# Power_Distro_Board.net
KiCad netlist of a schematic drawn in EAGLE
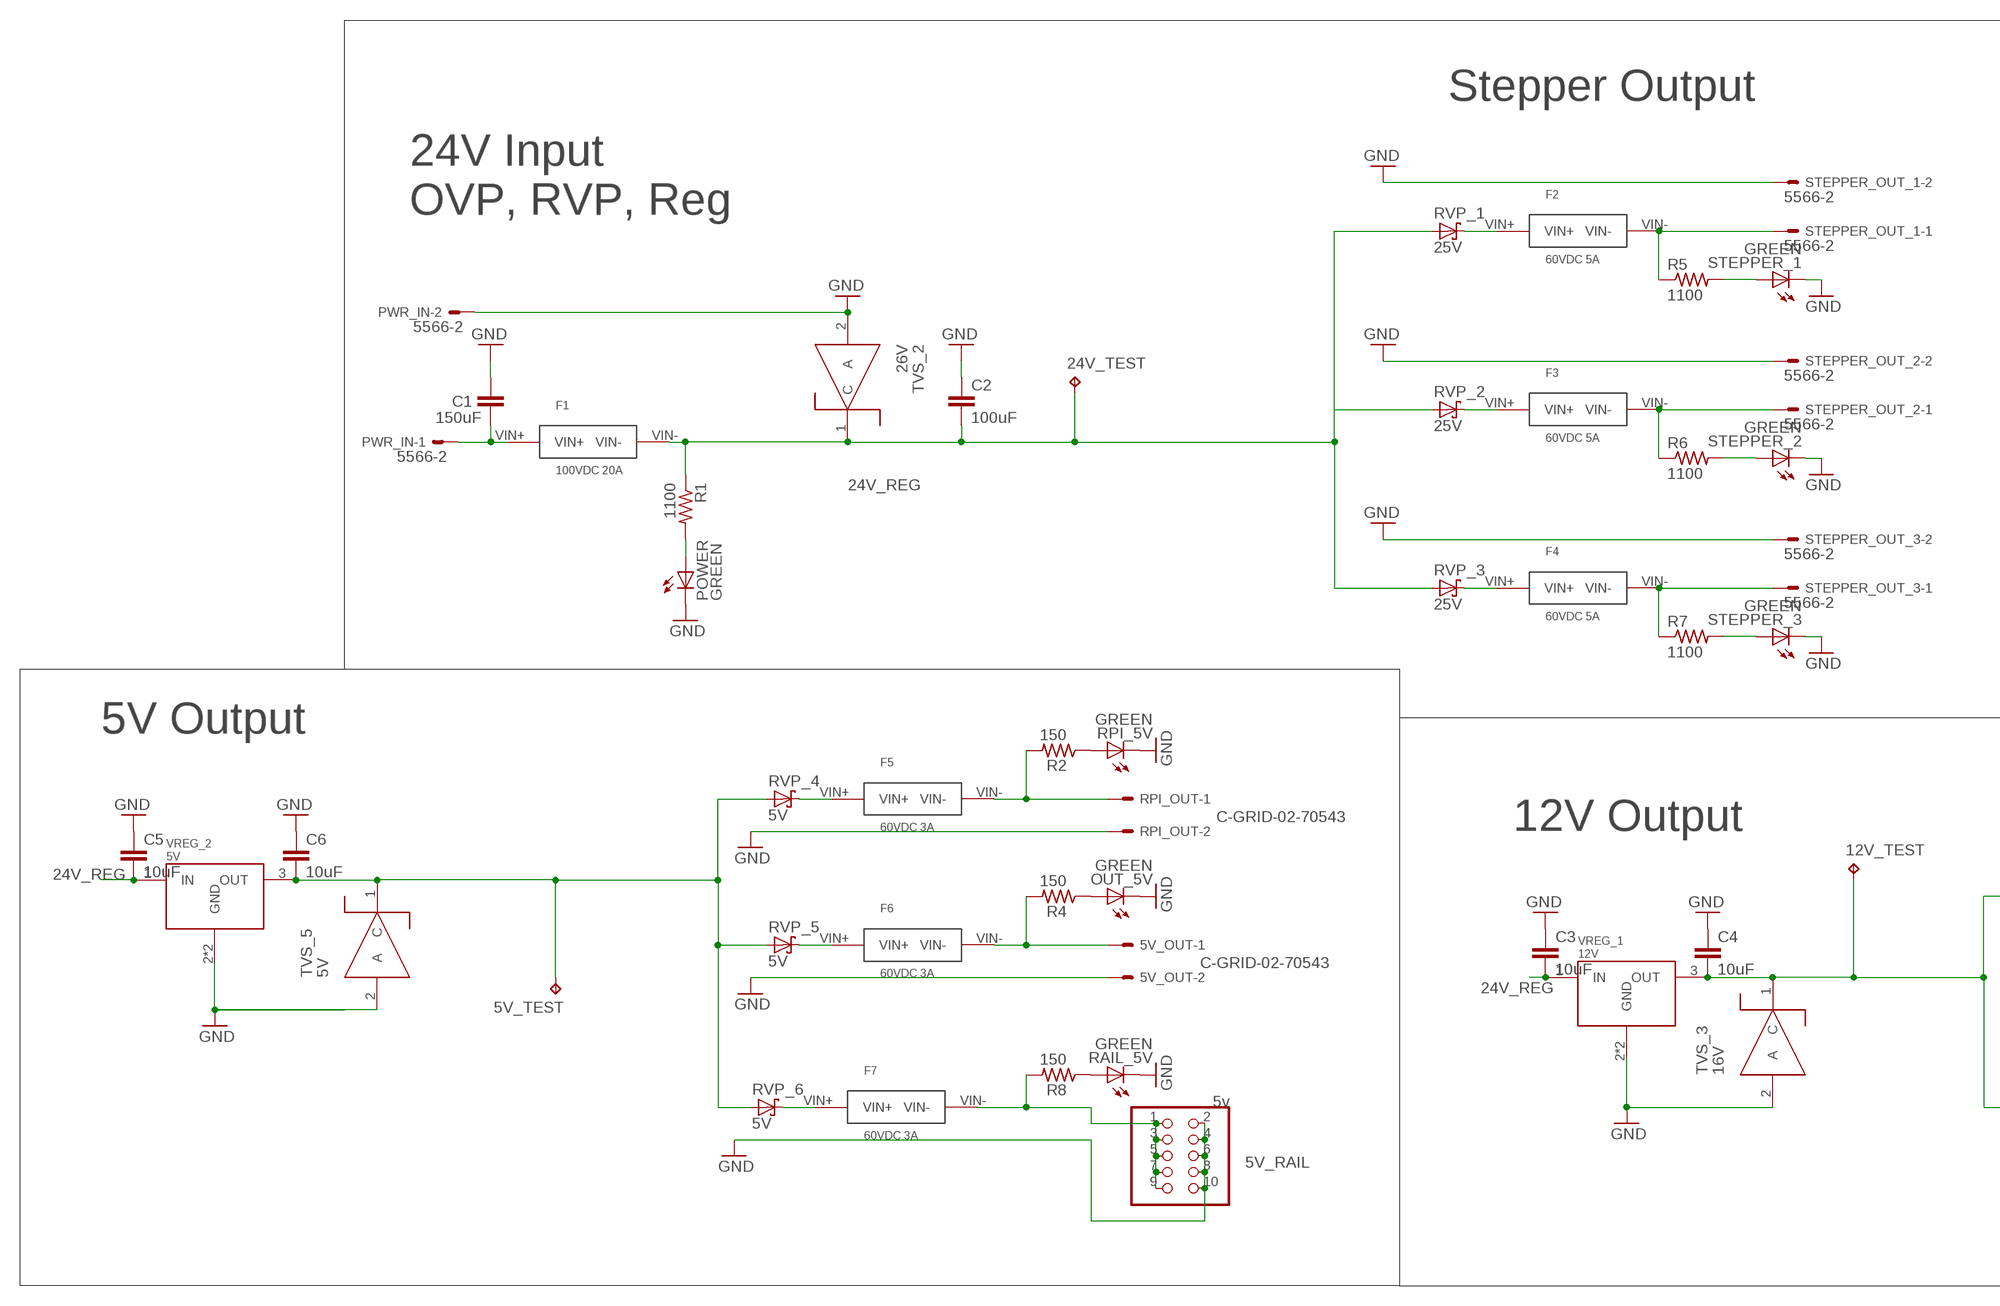
[diagram p0: schematic, sheet 1, part 1 of 2]
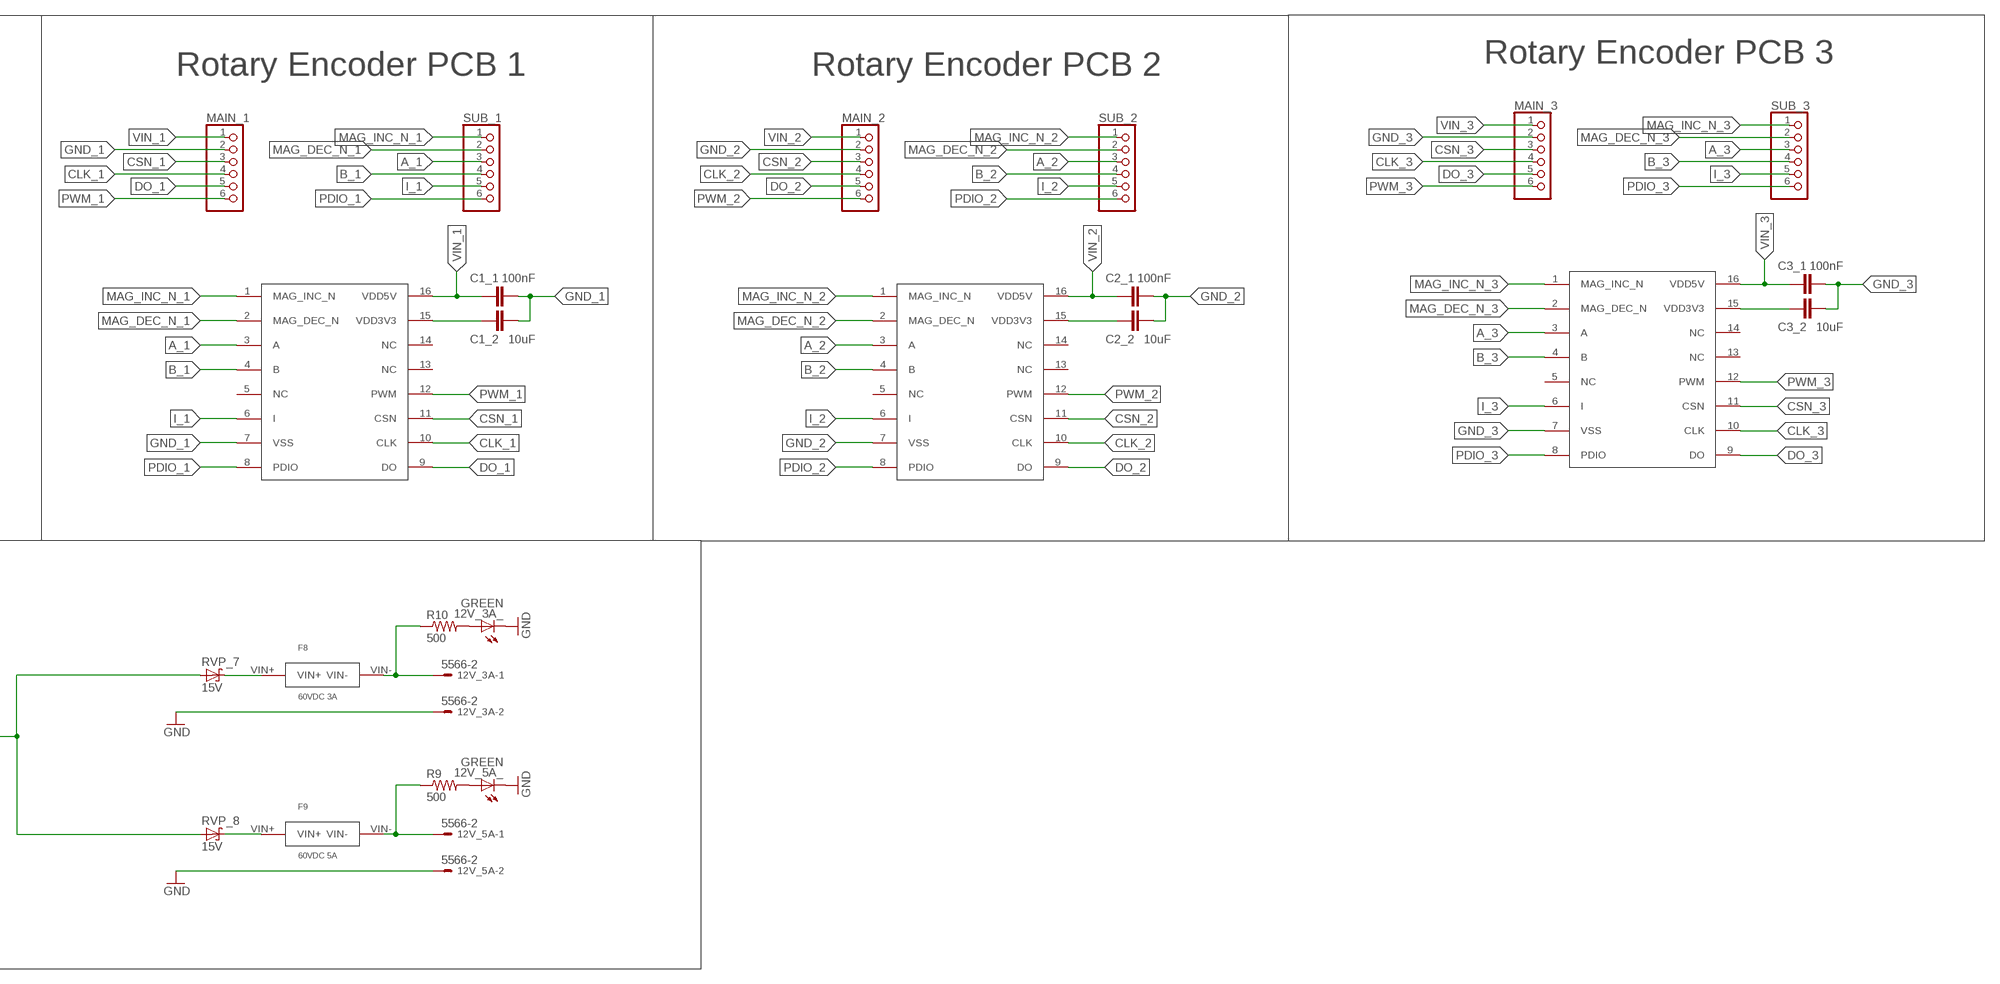
[diagram p1: schematic, sheet 1, part 2 of 2]

(export (version "E")
  (design (tool "Eeschema 10.0.6"))
  (components
    (comp (ref "5V_OUT")
      (value "C-GRID-02-70543")
      (footprint "eagle-import:70543-02")
      (libsource (lib "eagle-import") (part "C-GRID-02-70543"))
    )
    (comp (ref "5V_RAIL")
      (value "5v")
      (footprint "eagle-import:2X05")
      (libsource (lib "eagle-import") (part "PINHD-2X5"))
    )
    (comp (ref "5V_TEST")
      (value "TPPAD1-13")
      (footprint "eagle-import:P1-13")
      (libsource (lib "eagle-import") (part "TPPAD1-13"))
    )
    (comp (ref "12V_3A")
      (value "5566-2")
      (footprint "eagle-import:5566-2")
      (libsource (lib "eagle-import") (part "5566-2"))
    )
    (comp (ref "12V_3A_")
      (value "GREEN")
      (footprint "eagle-import:SML1206")
      (libsource (lib "eagle-import") (part "LEDSML1206"))
    )
    (comp (ref "12V_5A")
      (value "5566-2")
      (footprint "eagle-import:5566-2")
      (libsource (lib "eagle-import") (part "5566-2"))
    )
    (comp (ref "12V_5A_")
      (value "GREEN")
      (footprint "eagle-import:SML1206")
      (libsource (lib "eagle-import") (part "LEDSML1206"))
    )
    (comp (ref "12V_TEST")
      (value "TPPAD1-13")
      (footprint "eagle-import:P1-13")
      (libsource (lib "eagle-import") (part "TPPAD1-13"))
    )
    (comp (ref "24V_TEST")
      (value "TPPAD1-13")
      (footprint "eagle-import:P1-13")
      (libsource (lib "eagle-import") (part "TPPAD1-13"))
    )
    (comp (ref "C1")
      (value "150uF")
      (footprint "eagle-import:C1206")
      (libsource (lib "eagle-import") (part "C-EUC1206"))
    )
    (comp (ref "C1_1")
      (value "100nF")
      (footprint "eagle-import:C1206")
      (libsource (lib "eagle-import") (part "C-EUC1206"))
    )
    (comp (ref "C1_2")
      (value "10uF")
      (footprint "eagle-import:C1206")
      (libsource (lib "eagle-import") (part "C-EUC1206"))
    )
    (comp (ref "C2")
      (value "100uF")
      (footprint "eagle-import:C1206")
      (libsource (lib "eagle-import") (part "C-EUC1206"))
    )
    (comp (ref "C2_1")
      (value "100nF")
      (footprint "eagle-import:C1206")
      (libsource (lib "eagle-import") (part "C-EUC1206"))
    )
    (comp (ref "C2_2")
      (value "10uF")
      (footprint "eagle-import:C1206")
      (libsource (lib "eagle-import") (part "C-EUC1206"))
    )
    (comp (ref "C3")
      (value "10uF")
      (footprint "eagle-import:C1206")
      (libsource (lib "eagle-import") (part "C-EUC1206"))
    )
    (comp (ref "C3_1")
      (value "100nF")
      (footprint "eagle-import:C1206")
      (libsource (lib "eagle-import") (part "C-EUC1206"))
    )
    (comp (ref "C3_2")
      (value "10uF")
      (footprint "eagle-import:C1206")
      (libsource (lib "eagle-import") (part "C-EUC1206"))
    )
    (comp (ref "C4")
      (value "10uF")
      (footprint "eagle-import:C1206")
      (libsource (lib "eagle-import") (part "C-EUC1206"))
    )
    (comp (ref "C5")
      (value "10uF")
      (footprint "eagle-import:C1206")
      (libsource (lib "eagle-import") (part "C-EUC1206"))
    )
    (comp (ref "C6")
      (value "10uF")
      (footprint "eagle-import:C1206")
      (libsource (lib "eagle-import") (part "C-EUC1206"))
    )
    (comp (ref "ENC_1")
      (value "ENCODER_AS5045B")
      (footprint "eagle-import:SSOP16")
      (libsource (lib "eagle-import") (part "ENCODER_AS5045B"))
    )
    (comp (ref "ENC_2")
      (value "ENCODER_AS5045B")
      (footprint "eagle-import:SSOP16")
      (libsource (lib "eagle-import") (part "ENCODER_AS5045B"))
    )
    (comp (ref "ENC_3")
      (value "ENCODER_AS5045B")
      (footprint "eagle-import:SSOP16")
      (libsource (lib "eagle-import") (part "ENCODER_AS5045B"))
    )
    (comp (ref "F1")
      (value "100VDC 20A")
      (footprint "eagle-import:NANO")
      (libsource (lib "eagle-import") (part "LITTLEFUSENANO463"))
    )
    (comp (ref "F2")
      (value "60VDC 5A")
      (footprint "eagle-import:OMNI_BLOCK")
      (libsource (lib "eagle-import") (part "LITTLEFUSE0154"))
    )
    (comp (ref "F3")
      (value "60VDC 5A")
      (footprint "eagle-import:OMNI_BLOCK")
      (libsource (lib "eagle-import") (part "LITTLEFUSE0154"))
    )
    (comp (ref "F4")
      (value "60VDC 5A")
      (footprint "eagle-import:OMNI_BLOCK")
      (libsource (lib "eagle-import") (part "LITTLEFUSE0154"))
    )
    (comp (ref "F5")
      (value "60VDC 3A")
      (footprint "eagle-import:OMNI_BLOCK")
      (libsource (lib "eagle-import") (part "LITTLEFUSE0154"))
    )
    (comp (ref "F6")
      (value "60VDC 3A")
      (footprint "eagle-import:OMNI_BLOCK")
      (libsource (lib "eagle-import") (part "LITTLEFUSE0154"))
    )
    (comp (ref "F7")
      (value "60VDC 3A")
      (footprint "eagle-import:OMNI_BLOCK")
      (libsource (lib "eagle-import") (part "LITTLEFUSE0154"))
    )
    (comp (ref "F8")
      (value "60VDC 3A")
      (footprint "eagle-import:OMNI_BLOCK")
      (libsource (lib "eagle-import") (part "LITTLEFUSE0154"))
    )
    (comp (ref "F9")
      (value "60VDC 5A")
      (footprint "eagle-import:OMNI_BLOCK")
      (libsource (lib "eagle-import") (part "LITTLEFUSE0154"))
    )
    (comp (ref "MAIN_1")
      (value "PINHD-1X6")
      (footprint "eagle-import:1X06")
      (libsource (lib "eagle-import") (part "PINHD-1X6"))
    )
    (comp (ref "MAIN_2")
      (value "PINHD-1X6")
      (footprint "eagle-import:1X06")
      (libsource (lib "eagle-import") (part "PINHD-1X6"))
    )
    (comp (ref "MAIN_3")
      (value "PINHD-1X6")
      (footprint "eagle-import:1X06")
      (libsource (lib "eagle-import") (part "PINHD-1X6"))
    )
    (comp (ref "OUT_5V")
      (value "GREEN")
      (footprint "eagle-import:SML1206")
      (libsource (lib "eagle-import") (part "LEDSML1206"))
    )
    (comp (ref "POWER")
      (value "GREEN")
      (footprint "eagle-import:SML1206")
      (libsource (lib "eagle-import") (part "LEDSML1206"))
    )
    (comp (ref "PWR_IN")
      (value "5566-2")
      (footprint "eagle-import:5566-2")
      (libsource (lib "eagle-import") (part "5566-2"))
    )
    (comp (ref "R1")
      (value "1100")
      (footprint "eagle-import:R1206")
      (libsource (lib "eagle-import") (part "R-US_R1206"))
    )
    (comp (ref "R2")
      (value "150")
      (footprint "eagle-import:R1206")
      (libsource (lib "eagle-import") (part "R-US_R1206"))
    )
    (comp (ref "R4")
      (value "150")
      (footprint "eagle-import:R1206")
      (libsource (lib "eagle-import") (part "R-US_R1206"))
    )
    (comp (ref "R5")
      (value "1100")
      (footprint "eagle-import:R1206")
      (libsource (lib "eagle-import") (part "R-US_R1206"))
    )
    (comp (ref "R6")
      (value "1100")
      (footprint "eagle-import:R1206")
      (libsource (lib "eagle-import") (part "R-US_R1206"))
    )
    (comp (ref "R7")
      (value "1100")
      (footprint "eagle-import:R1206")
      (libsource (lib "eagle-import") (part "R-US_R1206"))
    )
    (comp (ref "R8")
      (value "150")
      (footprint "eagle-import:R1206")
      (libsource (lib "eagle-import") (part "R-US_R1206"))
    )
    (comp (ref "R9")
      (value "500")
      (footprint "eagle-import:R1206")
      (libsource (lib "eagle-import") (part "R-US_R1206"))
    )
    (comp (ref "R10")
      (value "500")
      (footprint "eagle-import:R1206")
      (libsource (lib "eagle-import") (part "R-US_R1206"))
    )
    (comp (ref "RAIL_5V")
      (value "GREEN")
      (footprint "eagle-import:SML1206")
      (libsource (lib "eagle-import") (part "LEDSML1206"))
    )
    (comp (ref "RPI_5V")
      (value "GREEN")
      (footprint "eagle-import:SML1206")
      (libsource (lib "eagle-import") (part "LEDSML1206"))
    )
    (comp (ref "RPI_OUT")
      (value "C-GRID-02-70543")
      (footprint "eagle-import:70543-02")
      (libsource (lib "eagle-import") (part "C-GRID-02-70543"))
    )
    (comp (ref "RVP_1")
      (value "25V")
      (footprint "eagle-import:SMC")
      (libsource (lib "eagle-import") (part "SCHOTTKY-DIODESMC"))
    )
    (comp (ref "RVP_2")
      (value "25V")
      (footprint "eagle-import:SMC")
      (libsource (lib "eagle-import") (part "SCHOTTKY-DIODESMC"))
    )
    (comp (ref "RVP_3")
      (value "25V")
      (footprint "eagle-import:SMC")
      (libsource (lib "eagle-import") (part "SCHOTTKY-DIODESMC"))
    )
    (comp (ref "RVP_4")
      (value "5V")
      (footprint "eagle-import:SMC")
      (libsource (lib "eagle-import") (part "SCHOTTKY-DIODESMC"))
    )
    (comp (ref "RVP_5")
      (value "5V")
      (footprint "eagle-import:SMC")
      (libsource (lib "eagle-import") (part "SCHOTTKY-DIODESMC"))
    )
    (comp (ref "RVP_6")
      (value "5V")
      (footprint "eagle-import:SMC")
      (libsource (lib "eagle-import") (part "SCHOTTKY-DIODESMC"))
    )
    (comp (ref "RVP_7")
      (value "15V")
      (footprint "eagle-import:SMC")
      (libsource (lib "eagle-import") (part "SCHOTTKY-DIODESMC"))
    )
    (comp (ref "RVP_8")
      (value "15V")
      (footprint "eagle-import:SMC")
      (libsource (lib "eagle-import") (part "SCHOTTKY-DIODESMC"))
    )
    (comp (ref "STEPPER_1")
      (value "GREEN")
      (footprint "eagle-import:SML1206")
      (libsource (lib "eagle-import") (part "LEDSML1206"))
    )
    (comp (ref "STEPPER_2")
      (value "GREEN")
      (footprint "eagle-import:SML1206")
      (libsource (lib "eagle-import") (part "LEDSML1206"))
    )
    (comp (ref "STEPPER_3")
      (value "GREEN")
      (footprint "eagle-import:SML1206")
      (libsource (lib "eagle-import") (part "LEDSML1206"))
    )
    (comp (ref "STEPPER_OUT_1")
      (value "5566-2")
      (footprint "eagle-import:5566-2")
      (libsource (lib "eagle-import") (part "5566-2"))
    )
    (comp (ref "STEPPER_OUT_2")
      (value "5566-2")
      (footprint "eagle-import:5566-2")
      (libsource (lib "eagle-import") (part "5566-2"))
    )
    (comp (ref "STEPPER_OUT_3")
      (value "5566-2")
      (footprint "eagle-import:5566-2")
      (libsource (lib "eagle-import") (part "5566-2"))
    )
    (comp (ref "SUB_1")
      (value "PINHD-1X6")
      (footprint "eagle-import:1X06")
      (libsource (lib "eagle-import") (part "PINHD-1X6"))
    )
    (comp (ref "SUB_2")
      (value "PINHD-1X6")
      (footprint "eagle-import:1X06")
      (libsource (lib "eagle-import") (part "PINHD-1X6"))
    )
    (comp (ref "SUB_3")
      (value "PINHD-1X6")
      (footprint "eagle-import:1X06")
      (libsource (lib "eagle-import") (part "PINHD-1X6"))
    )
    (comp (ref "TVS_2")
      (value "26V")
      (footprint "eagle-import:DO-214AC")
      (libsource (lib "eagle-import") (part "SMAJ26A_TVSSMA"))
    )
    (comp (ref "TVS_3")
      (value "16V")
      (footprint "eagle-import:DO-214AC")
      (libsource (lib "eagle-import") (part "PRSMA16_TVS"))
    )
    (comp (ref "TVS_5")
      (value "5V")
      (footprint "eagle-import:DO-214AC")
      (libsource (lib "eagle-import") (part "SMAJ5.0_TVSSMA"))
    )
    (comp (ref "VREG_1")
      (value "12V")
      (footprint "eagle-import:TO-263-3")
      (libsource (lib "eagle-import") (part "HIGH-CURRENT_REGSMA"))
    )
    (comp (ref "VREG_2")
      (value "5V")
      (footprint "eagle-import:TO-263-3")
      (libsource (lib "eagle-import") (part "HIGH-CURRENT_REGSMA"))
    )
  )
  (nets
    (net (code "1") (name "/24V_REG") (class "Default")
      (node (ref "24V_TEST") (pin "TP") (pinfunction "TP_TP") (pintype "input"))
      (node (ref "C2") (pin "2") (pinfunction "2_2") (pintype "passive"))
      (node (ref "C3") (pin "2") (pinfunction "2_2") (pintype "passive"))
      (node (ref "C5") (pin "2") (pinfunction "2_2") (pintype "passive"))
      (node (ref "F1") (pin "VIN-") (pinfunction "VIN-_VIN-") (pintype "bidirectional"))
      (node (ref "R1") (pin "1") (pinfunction "1_1") (pintype "passive"))
      (node (ref "RVP_1") (pin "A") (pinfunction "A_A") (pintype "passive"))
      (node (ref "RVP_2") (pin "A") (pinfunction "A_A") (pintype "passive"))
      (node (ref "RVP_3") (pin "A") (pinfunction "A_A") (pintype "passive"))
      (node (ref "TVS_2") (pin "1") (pinfunction "C_1") (pintype "bidirectional"))
      (node (ref "VREG_1") (pin "1") (pinfunction "IN_1") (pintype "bidirectional"))
      (node (ref "VREG_2") (pin "1") (pinfunction "IN_1") (pintype "bidirectional"))
    )
    (net (code "2") (name "A_1") (class "Default")
      (node (ref "ENC_1") (pin "3") (pinfunction "A_3") (pintype "bidirectional"))
      (node (ref "SUB_1") (pin "3") (pinfunction "3_3") (pintype "passive"))
    )
    (net (code "3") (name "A_2") (class "Default")
      (node (ref "ENC_2") (pin "3") (pinfunction "A_3") (pintype "bidirectional"))
      (node (ref "SUB_2") (pin "3") (pinfunction "3_3") (pintype "passive"))
    )
    (net (code "4") (name "A_3") (class "Default")
      (node (ref "ENC_3") (pin "3") (pinfunction "A_3") (pintype "bidirectional"))
      (node (ref "SUB_3") (pin "3") (pinfunction "3_3") (pintype "passive"))
    )
    (net (code "5") (name "B_1") (class "Default")
      (node (ref "ENC_1") (pin "4") (pinfunction "B_4") (pintype "bidirectional"))
      (node (ref "SUB_1") (pin "4") (pinfunction "4_4") (pintype "passive"))
    )
    (net (code "6") (name "B_2") (class "Default")
      (node (ref "ENC_2") (pin "4") (pinfunction "B_4") (pintype "bidirectional"))
      (node (ref "SUB_2") (pin "4") (pinfunction "4_4") (pintype "passive"))
    )
    (net (code "7") (name "B_3") (class "Default")
      (node (ref "ENC_3") (pin "4") (pinfunction "B_4") (pintype "bidirectional"))
      (node (ref "SUB_3") (pin "4") (pinfunction "4_4") (pintype "passive"))
    )
    (net (code "8") (name "CLK_1") (class "Default")
      (node (ref "ENC_1") (pin "10") (pinfunction "CLK_10") (pintype "bidirectional"))
      (node (ref "MAIN_1") (pin "4") (pinfunction "4_4") (pintype "passive"))
    )
    (net (code "9") (name "CLK_2") (class "Default")
      (node (ref "ENC_2") (pin "10") (pinfunction "CLK_10") (pintype "bidirectional"))
      (node (ref "MAIN_2") (pin "4") (pinfunction "4_4") (pintype "passive"))
    )
    (net (code "10") (name "CLK_3") (class "Default")
      (node (ref "ENC_3") (pin "10") (pinfunction "CLK_10") (pintype "bidirectional"))
      (node (ref "MAIN_3") (pin "4") (pinfunction "4_4") (pintype "passive"))
    )
    (net (code "11") (name "CSN_1") (class "Default")
      (node (ref "ENC_1") (pin "11") (pinfunction "CSN_11") (pintype "bidirectional"))
      (node (ref "MAIN_1") (pin "3") (pinfunction "3_3") (pintype "passive"))
    )
    (net (code "12") (name "CSN_2") (class "Default")
      (node (ref "ENC_2") (pin "11") (pinfunction "CSN_11") (pintype "bidirectional"))
      (node (ref "MAIN_2") (pin "3") (pinfunction "3_3") (pintype "passive"))
    )
    (net (code "13") (name "CSN_3") (class "Default")
      (node (ref "ENC_3") (pin "11") (pinfunction "CSN_11") (pintype "bidirectional"))
      (node (ref "MAIN_3") (pin "3") (pinfunction "3_3") (pintype "passive"))
    )
    (net (code "14") (name "DO_1") (class "Default")
      (node (ref "ENC_1") (pin "9") (pinfunction "DO_9") (pintype "bidirectional"))
      (node (ref "MAIN_1") (pin "5") (pinfunction "5_5") (pintype "passive"))
    )
    (net (code "15") (name "DO_2") (class "Default")
      (node (ref "ENC_2") (pin "9") (pinfunction "DO_9") (pintype "bidirectional"))
      (node (ref "MAIN_2") (pin "5") (pinfunction "5_5") (pintype "passive"))
    )
    (net (code "16") (name "DO_3") (class "Default")
      (node (ref "ENC_3") (pin "9") (pinfunction "DO_9") (pintype "bidirectional"))
      (node (ref "MAIN_3") (pin "5") (pinfunction "5_5") (pintype "passive"))
    )
    (net (code "17") (name "GND") (class "Default")
      (node (ref "12V_3A") (pin "2") (pinfunction "S_2") (pintype "passive"))
      (node (ref "12V_3A_") (pin "C") (pinfunction "C_C") (pintype "passive"))
      (node (ref "12V_5A") (pin "2") (pinfunction "S_2") (pintype "passive"))
      (node (ref "12V_5A_") (pin "C") (pinfunction "C_C") (pintype "passive"))
      (node (ref "5V_OUT") (pin "2") (pinfunction "S_2") (pintype "passive"))
      (node (ref "5V_RAIL") (pin "10") (pinfunction "10_10") (pintype "passive"))
      (node (ref "5V_RAIL") (pin "2") (pinfunction "2_2") (pintype "passive"))
      (node (ref "5V_RAIL") (pin "4") (pinfunction "4_4") (pintype "passive"))
      (node (ref "5V_RAIL") (pin "6") (pinfunction "6_6") (pintype "passive"))
      (node (ref "5V_RAIL") (pin "8") (pinfunction "8_8") (pintype "passive"))
      (node (ref "C1") (pin "1") (pinfunction "1_1") (pintype "passive"))
      (node (ref "C2") (pin "1") (pinfunction "1_1") (pintype "passive"))
      (node (ref "C3") (pin "1") (pinfunction "1_1") (pintype "passive"))
      (node (ref "C4") (pin "1") (pinfunction "1_1") (pintype "passive"))
      (node (ref "C5") (pin "1") (pinfunction "1_1") (pintype "passive"))
      (node (ref "C6") (pin "1") (pinfunction "1_1") (pintype "passive"))
      (node (ref "OUT_5V") (pin "C") (pinfunction "C_C") (pintype "passive"))
      (node (ref "POWER") (pin "C") (pinfunction "C_C") (pintype "passive"))
      (node (ref "PWR_IN") (pin "2") (pinfunction "S_2") (pintype "passive"))
      (node (ref "RAIL_5V") (pin "C") (pinfunction "C_C") (pintype "passive"))
      (node (ref "RPI_5V") (pin "C") (pinfunction "C_C") (pintype "passive"))
      (node (ref "RPI_OUT") (pin "2") (pinfunction "S_2") (pintype "passive"))
      (node (ref "STEPPER_1") (pin "C") (pinfunction "C_C") (pintype "passive"))
      (node (ref "STEPPER_2") (pin "C") (pinfunction "C_C") (pintype "passive"))
      (node (ref "STEPPER_3") (pin "C") (pinfunction "C_C") (pintype "passive"))
      (node (ref "STEPPER_OUT_1") (pin "2") (pinfunction "S_2") (pintype "passive"))
      (node (ref "STEPPER_OUT_2") (pin "2") (pinfunction "S_2") (pintype "passive"))
      (node (ref "STEPPER_OUT_3") (pin "2") (pinfunction "S_2") (pintype "passive"))
      (node (ref "TVS_2") (pin "2") (pinfunction "A_2") (pintype "bidirectional"))
      (node (ref "TVS_3") (pin "2") (pinfunction "A_2") (pintype "bidirectional"))
      (node (ref "TVS_5") (pin "2") (pinfunction "A_2") (pintype "bidirectional"))
      (node (ref "VREG_1") (pin "2") (pinfunction "GND_2") (pintype "bidirectional"))
      (node (ref "VREG_1") (pin "4") (pinfunction "GND_4") (pintype "bidirectional"))
      (node (ref "VREG_2") (pin "2") (pinfunction "GND_2") (pintype "bidirectional"))
      (node (ref "VREG_2") (pin "4") (pinfunction "GND_4") (pintype "bidirectional"))
    )
    (net (code "18") (name "GND_1") (class "Default")
      (node (ref "C1_1") (pin "2") (pinfunction "2_2") (pintype "passive"))
      (node (ref "C1_2") (pin "2") (pinfunction "2_2") (pintype "passive"))
      (node (ref "ENC_1") (pin "7") (pinfunction "VSS_7") (pintype "bidirectional"))
      (node (ref "MAIN_1") (pin "2") (pinfunction "2_2") (pintype "passive"))
    )
    (net (code "19") (name "GND_2") (class "Default")
      (node (ref "C2_1") (pin "2") (pinfunction "2_2") (pintype "passive"))
      (node (ref "C2_2") (pin "2") (pinfunction "2_2") (pintype "passive"))
      (node (ref "ENC_2") (pin "7") (pinfunction "VSS_7") (pintype "bidirectional"))
      (node (ref "MAIN_2") (pin "2") (pinfunction "2_2") (pintype "passive"))
    )
    (net (code "20") (name "GND_3") (class "Default")
      (node (ref "C3_1") (pin "2") (pinfunction "2_2") (pintype "passive"))
      (node (ref "C3_2") (pin "2") (pinfunction "2_2") (pintype "passive"))
      (node (ref "ENC_3") (pin "7") (pinfunction "VSS_7") (pintype "bidirectional"))
      (node (ref "MAIN_3") (pin "2") (pinfunction "2_2") (pintype "passive"))
    )
    (net (code "21") (name "I_1") (class "Default")
      (node (ref "ENC_1") (pin "6") (pinfunction "I_6") (pintype "bidirectional"))
      (node (ref "SUB_1") (pin "5") (pinfunction "5_5") (pintype "passive"))
    )
    (net (code "22") (name "I_2") (class "Default")
      (node (ref "ENC_2") (pin "6") (pinfunction "I_6") (pintype "bidirectional"))
      (node (ref "SUB_2") (pin "5") (pinfunction "5_5") (pintype "passive"))
    )
    (net (code "23") (name "I_3") (class "Default")
      (node (ref "ENC_3") (pin "6") (pinfunction "I_6") (pintype "bidirectional"))
      (node (ref "SUB_3") (pin "5") (pinfunction "5_5") (pintype "passive"))
    )
    (net (code "24") (name "MAG_DEC_N_1") (class "Default")
      (node (ref "ENC_1") (pin "2") (pinfunction "MAG_DEC_N_2") (pintype "bidirectional"))
      (node (ref "SUB_1") (pin "2") (pinfunction "2_2") (pintype "passive"))
    )
    (net (code "25") (name "MAG_DEC_N_2") (class "Default")
      (node (ref "ENC_2") (pin "2") (pinfunction "MAG_DEC_N_2") (pintype "bidirectional"))
      (node (ref "SUB_2") (pin "2") (pinfunction "2_2") (pintype "passive"))
    )
    (net (code "26") (name "MAG_DEC_N_3") (class "Default")
      (node (ref "ENC_3") (pin "2") (pinfunction "MAG_DEC_N_2") (pintype "bidirectional"))
      (node (ref "SUB_3") (pin "2") (pinfunction "2_2") (pintype "passive"))
    )
    (net (code "27") (name "MAG_INC_N_1") (class "Default")
      (node (ref "ENC_1") (pin "1") (pinfunction "MAG_INC_N_1") (pintype "bidirectional"))
      (node (ref "SUB_1") (pin "1") (pinfunction "1_1") (pintype "passive"))
    )
    (net (code "28") (name "MAG_INC_N_2") (class "Default")
      (node (ref "ENC_2") (pin "1") (pinfunction "MAG_INC_N_1") (pintype "bidirectional"))
      (node (ref "SUB_2") (pin "1") (pinfunction "1_1") (pintype "passive"))
    )
    (net (code "29") (name "MAG_INC_N_3") (class "Default")
      (node (ref "ENC_3") (pin "1") (pinfunction "MAG_INC_N_1") (pintype "bidirectional"))
      (node (ref "SUB_3") (pin "1") (pinfunction "1_1") (pintype "passive"))
    )
    (net (code "30") (name "Net-(5V_OUTA-S)") (class "Default")
      (node (ref "5V_OUT") (pin "1") (pinfunction "S_1") (pintype "passive"))
      (node (ref "F6") (pin "VIN-") (pinfunction "VIN-_VIN-") (pintype "bidirectional"))
      (node (ref "R4") (pin "2") (pinfunction "2_2") (pintype "passive"))
    )
    (net (code "31") (name "Net-(5V_RAIL-Pad1)") (class "Default")
      (node (ref "5V_RAIL") (pin "1") (pinfunction "1_1") (pintype "passive"))
      (node (ref "5V_RAIL") (pin "3") (pinfunction "3_3") (pintype "passive"))
      (node (ref "5V_RAIL") (pin "5") (pinfunction "5_5") (pintype "passive"))
      (node (ref "5V_RAIL") (pin "7") (pinfunction "7_7") (pintype "passive"))
      (node (ref "5V_RAIL") (pin "9") (pinfunction "9_9") (pintype "passive"))
      (node (ref "F7") (pin "VIN-") (pinfunction "VIN-_VIN-") (pintype "bidirectional"))
      (node (ref "R8") (pin "2") (pinfunction "2_2") (pintype "passive"))
    )
    (net (code "32") (name "Net-(12V_3AA-S)") (class "Default")
      (node (ref "12V_3A") (pin "1") (pinfunction "S_1") (pintype "passive"))
      (node (ref "F8") (pin "VIN-") (pinfunction "VIN-_VIN-") (pintype "bidirectional"))
      (node (ref "R10") (pin "1") (pinfunction "1_1") (pintype "passive"))
    )
    (net (code "33") (name "Net-(12V_3A_-PadA)") (class "Default")
      (node (ref "12V_3A_") (pin "A") (pinfunction "A_A") (pintype "passive"))
      (node (ref "R10") (pin "2") (pinfunction "2_2") (pintype "passive"))
    )
    (net (code "34") (name "Net-(12V_5AA-S)") (class "Default")
      (node (ref "12V_5A") (pin "1") (pinfunction "S_1") (pintype "passive"))
      (node (ref "F9") (pin "VIN-") (pinfunction "VIN-_VIN-") (pintype "bidirectional"))
      (node (ref "R9") (pin "1") (pinfunction "1_1") (pintype "passive"))
    )
    (net (code "35") (name "Net-(12V_5A_-PadA)") (class "Default")
      (node (ref "12V_5A_") (pin "A") (pinfunction "A_A") (pintype "passive"))
      (node (ref "R9") (pin "2") (pinfunction "2_2") (pintype "passive"))
    )
    (net (code "36") (name "Net-(ENC_1-VDD3V3)") (class "Default")
      (node (ref "C1_2") (pin "1") (pinfunction "1_1") (pintype "passive"))
      (node (ref "ENC_1") (pin "15") (pinfunction "VDD3V3_15") (pintype "bidirectional"))
    )
    (net (code "37") (name "Net-(ENC_2-VDD3V3)") (class "Default")
      (node (ref "C2_2") (pin "1") (pinfunction "1_1") (pintype "passive"))
      (node (ref "ENC_2") (pin "15") (pinfunction "VDD3V3_15") (pintype "bidirectional"))
    )
    (net (code "38") (name "Net-(ENC_3-VDD3V3)") (class "Default")
      (node (ref "C3_2") (pin "1") (pinfunction "1_1") (pintype "passive"))
      (node (ref "ENC_3") (pin "15") (pinfunction "VDD3V3_15") (pintype "bidirectional"))
    )
    (net (code "39") (name "Net-(F2-PadVIN+)") (class "Default")
      (node (ref "F2") (pin "VIN+") (pinfunction "VIN+_VIN+") (pintype "bidirectional"))
      (node (ref "RVP_1") (pin "C") (pinfunction "C_C") (pintype "passive"))
    )
    (net (code "40") (name "Net-(F3-PadVIN+)") (class "Default")
      (node (ref "F3") (pin "VIN+") (pinfunction "VIN+_VIN+") (pintype "bidirectional"))
      (node (ref "RVP_2") (pin "C") (pinfunction "C_C") (pintype "passive"))
    )
    (net (code "41") (name "Net-(F4-PadVIN+)") (class "Default")
      (node (ref "F4") (pin "VIN+") (pinfunction "VIN+_VIN+") (pintype "bidirectional"))
      (node (ref "RVP_3") (pin "C") (pinfunction "C_C") (pintype "passive"))
    )
    (net (code "42") (name "Net-(F5-PadVIN+)") (class "Default")
      (node (ref "F5") (pin "VIN+") (pinfunction "VIN+_VIN+") (pintype "bidirectional"))
      (node (ref "RVP_4") (pin "C") (pinfunction "C_C") (pintype "passive"))
    )
    (net (code "43") (name "Net-(F6-PadVIN+)") (class "Default")
      (node (ref "F6") (pin "VIN+") (pinfunction "VIN+_VIN+") (pintype "bidirectional"))
      (node (ref "RVP_5") (pin "C") (pinfunction "C_C") (pintype "passive"))
    )
    (net (code "44") (name "Net-(F7-PadVIN+)") (class "Default")
      (node (ref "F7") (pin "VIN+") (pinfunction "VIN+_VIN+") (pintype "bidirectional"))
      (node (ref "RVP_6") (pin "C") (pinfunction "C_C") (pintype "passive"))
    )
    (net (code "45") (name "Net-(F8-PadVIN+)") (class "Default")
      (node (ref "F8") (pin "VIN+") (pinfunction "VIN+_VIN+") (pintype "bidirectional"))
      (node (ref "RVP_7") (pin "C") (pinfunction "C_C") (pintype "passive"))
    )
    (net (code "46") (name "Net-(F9-PadVIN+)") (class "Default")
      (node (ref "F9") (pin "VIN+") (pinfunction "VIN+_VIN+") (pintype "bidirectional"))
      (node (ref "RVP_8") (pin "C") (pinfunction "C_C") (pintype "passive"))
    )
    (net (code "47") (name "Net-(OUT_5V-PadA)") (class "Default")
      (node (ref "OUT_5V") (pin "A") (pinfunction "A_A") (pintype "passive"))
      (node (ref "R4") (pin "1") (pinfunction "1_1") (pintype "passive"))
    )
    (net (code "48") (name "Net-(POWER-PadA)") (class "Default")
      (node (ref "POWER") (pin "A") (pinfunction "A_A") (pintype "passive"))
      (node (ref "R1") (pin "2") (pinfunction "2_2") (pintype "passive"))
    )
    (net (code "49") (name "Net-(PWR_INA-S)") (class "Default")
      (node (ref "C1") (pin "2") (pinfunction "2_2") (pintype "passive"))
      (node (ref "F1") (pin "VIN+") (pinfunction "VIN+_VIN+") (pintype "bidirectional"))
      (node (ref "PWR_IN") (pin "1") (pinfunction "S_1") (pintype "passive"))
    )
    (net (code "50") (name "Net-(R2-Pad1)") (class "Default")
      (node (ref "R2") (pin "1") (pinfunction "1_1") (pintype "passive"))
      (node (ref "RPI_5V") (pin "A") (pinfunction "A_A") (pintype "passive"))
    )
    (net (code "51") (name "Net-(R5-Pad2)") (class "Default")
      (node (ref "R5") (pin "2") (pinfunction "2_2") (pintype "passive"))
      (node (ref "STEPPER_1") (pin "A") (pinfunction "A_A") (pintype "passive"))
    )
    (net (code "52") (name "Net-(R6-Pad2)") (class "Default")
      (node (ref "R6") (pin "2") (pinfunction "2_2") (pintype "passive"))
      (node (ref "STEPPER_2") (pin "A") (pinfunction "A_A") (pintype "passive"))
    )
    (net (code "53") (name "Net-(R7-Pad2)") (class "Default")
      (node (ref "R7") (pin "2") (pinfunction "2_2") (pintype "passive"))
      (node (ref "STEPPER_3") (pin "A") (pinfunction "A_A") (pintype "passive"))
    )
    (net (code "54") (name "Net-(R8-Pad1)") (class "Default")
      (node (ref "R8") (pin "1") (pinfunction "1_1") (pintype "passive"))
      (node (ref "RAIL_5V") (pin "A") (pinfunction "A_A") (pintype "passive"))
    )
    (net (code "55") (name "Net-(RPI_OUTA-S)") (class "Default")
      (node (ref "F5") (pin "VIN-") (pinfunction "VIN-_VIN-") (pintype "bidirectional"))
      (node (ref "R2") (pin "2") (pinfunction "2_2") (pintype "passive"))
      (node (ref "RPI_OUT") (pin "1") (pinfunction "S_1") (pintype "passive"))
    )
    (net (code "56") (name "Net-(STEPPER_OUT_1A-S)") (class "Default")
      (node (ref "F2") (pin "VIN-") (pinfunction "VIN-_VIN-") (pintype "bidirectional"))
      (node (ref "R5") (pin "1") (pinfunction "1_1") (pintype "passive"))
      (node (ref "STEPPER_OUT_1") (pin "1") (pinfunction "S_1") (pintype "passive"))
    )
    (net (code "57") (name "Net-(STEPPER_OUT_2A-S)") (class "Default")
      (node (ref "F3") (pin "VIN-") (pinfunction "VIN-_VIN-") (pintype "bidirectional"))
      (node (ref "R6") (pin "1") (pinfunction "1_1") (pintype "passive"))
      (node (ref "STEPPER_OUT_2") (pin "1") (pinfunction "S_1") (pintype "passive"))
    )
    (net (code "58") (name "Net-(STEPPER_OUT_3A-S)") (class "Default")
      (node (ref "F4") (pin "VIN-") (pinfunction "VIN-_VIN-") (pintype "bidirectional"))
      (node (ref "R7") (pin "1") (pinfunction "1_1") (pintype "passive"))
      (node (ref "STEPPER_OUT_3") (pin "1") (pinfunction "S_1") (pintype "passive"))
    )
    (net (code "59") (name "Net-(TVS_3-C)") (class "Default")
      (node (ref "12V_TEST") (pin "TP") (pinfunction "TP_TP") (pintype "input"))
      (node (ref "C4") (pin "2") (pinfunction "2_2") (pintype "passive"))
      (node (ref "RVP_7") (pin "A") (pinfunction "A_A") (pintype "passive"))
      (node (ref "RVP_8") (pin "A") (pinfunction "A_A") (pintype "passive"))
      (node (ref "TVS_3") (pin "1") (pinfunction "C_1") (pintype "bidirectional"))
      (node (ref "VREG_1") (pin "3") (pinfunction "OUT_3") (pintype "bidirectional"))
    )
    (net (code "60") (name "Net-(TVS_5-C)") (class "Default")
      (node (ref "5V_TEST") (pin "TP") (pinfunction "TP_TP") (pintype "input"))
      (node (ref "C6") (pin "2") (pinfunction "2_2") (pintype "passive"))
      (node (ref "RVP_4") (pin "A") (pinfunction "A_A") (pintype "passive"))
      (node (ref "RVP_5") (pin "A") (pinfunction "A_A") (pintype "passive"))
      (node (ref "RVP_6") (pin "A") (pinfunction "A_A") (pintype "passive"))
      (node (ref "TVS_5") (pin "1") (pinfunction "C_1") (pintype "bidirectional"))
      (node (ref "VREG_2") (pin "3") (pinfunction "OUT_3") (pintype "bidirectional"))
    )
    (net (code "61") (name "PDIO_1") (class "Default")
      (node (ref "ENC_1") (pin "8") (pinfunction "PDIO_8") (pintype "bidirectional"))
      (node (ref "SUB_1") (pin "6") (pinfunction "6_6") (pintype "passive"))
    )
    (net (code "62") (name "PDIO_2") (class "Default")
      (node (ref "ENC_2") (pin "8") (pinfunction "PDIO_8") (pintype "bidirectional"))
      (node (ref "SUB_2") (pin "6") (pinfunction "6_6") (pintype "passive"))
    )
    (net (code "63") (name "PDIO_3") (class "Default")
      (node (ref "ENC_3") (pin "8") (pinfunction "PDIO_8") (pintype "bidirectional"))
      (node (ref "SUB_3") (pin "6") (pinfunction "6_6") (pintype "passive"))
    )
    (net (code "64") (name "PWM_1") (class "Default")
      (node (ref "ENC_1") (pin "12") (pinfunction "PWM_12") (pintype "bidirectional"))
      (node (ref "MAIN_1") (pin "6") (pinfunction "6_6") (pintype "passive"))
    )
    (net (code "65") (name "PWM_2") (class "Default")
      (node (ref "ENC_2") (pin "12") (pinfunction "PWM_12") (pintype "bidirectional"))
      (node (ref "MAIN_2") (pin "6") (pinfunction "6_6") (pintype "passive"))
    )
    (net (code "66") (name "PWM_3") (class "Default")
      (node (ref "ENC_3") (pin "12") (pinfunction "PWM_12") (pintype "bidirectional"))
      (node (ref "MAIN_3") (pin "6") (pinfunction "6_6") (pintype "passive"))
    )
    (net (code "67") (name "VIN_1") (class "Default")
      (node (ref "C1_1") (pin "1") (pinfunction "1_1") (pintype "passive"))
      (node (ref "ENC_1") (pin "16") (pinfunction "VDD5V_16") (pintype "bidirectional"))
      (node (ref "MAIN_1") (pin "1") (pinfunction "1_1") (pintype "passive"))
    )
    (net (code "68") (name "VIN_2") (class "Default")
      (node (ref "C2_1") (pin "1") (pinfunction "1_1") (pintype "passive"))
      (node (ref "ENC_2") (pin "16") (pinfunction "VDD5V_16") (pintype "bidirectional"))
      (node (ref "MAIN_2") (pin "1") (pinfunction "1_1") (pintype "passive"))
    )
    (net (code "69") (name "VIN_3") (class "Default")
      (node (ref "C3_1") (pin "1") (pinfunction "1_1") (pintype "passive"))
      (node (ref "ENC_3") (pin "16") (pinfunction "VDD5V_16") (pintype "bidirectional"))
      (node (ref "MAIN_3") (pin "1") (pinfunction "1_1") (pintype "passive"))
    )
    (net (code "70") (name "unconnected-(ENC_1-NC-Pad5)") (class "Default")
      (node (ref "ENC_1") (pin "5") (pinfunction "NC_5") (pintype "bidirectional"))
    )
    (net (code "71") (name "unconnected-(ENC_1-NC-Pad13)") (class "Default")
      (node (ref "ENC_1") (pin "13") (pinfunction "NC_13") (pintype "bidirectional"))
    )
    (net (code "72") (name "unconnected-(ENC_1-NC-Pad14)") (class "Default")
      (node (ref "ENC_1") (pin "14") (pinfunction "NC_14") (pintype "bidirectional"))
    )
    (net (code "73") (name "unconnected-(ENC_2-NC-Pad5)") (class "Default")
      (node (ref "ENC_2") (pin "5") (pinfunction "NC_5") (pintype "bidirectional"))
    )
    (net (code "74") (name "unconnected-(ENC_2-NC-Pad13)") (class "Default")
      (node (ref "ENC_2") (pin "13") (pinfunction "NC_13") (pintype "bidirectional"))
    )
    (net (code "75") (name "unconnected-(ENC_2-NC-Pad14)") (class "Default")
      (node (ref "ENC_2") (pin "14") (pinfunction "NC_14") (pintype "bidirectional"))
    )
    (net (code "76") (name "unconnected-(ENC_3-NC-Pad5)") (class "Default")
      (node (ref "ENC_3") (pin "5") (pinfunction "NC_5") (pintype "bidirectional"))
    )
    (net (code "77") (name "unconnected-(ENC_3-NC-Pad13)") (class "Default")
      (node (ref "ENC_3") (pin "13") (pinfunction "NC_13") (pintype "bidirectional"))
    )
    (net (code "78") (name "unconnected-(ENC_3-NC-Pad14)") (class "Default")
      (node (ref "ENC_3") (pin "14") (pinfunction "NC_14") (pintype "bidirectional"))
    )
  )
)
